# dram_lpddr4.net
KiCad netlist of a schematic drawn in Altium Designer
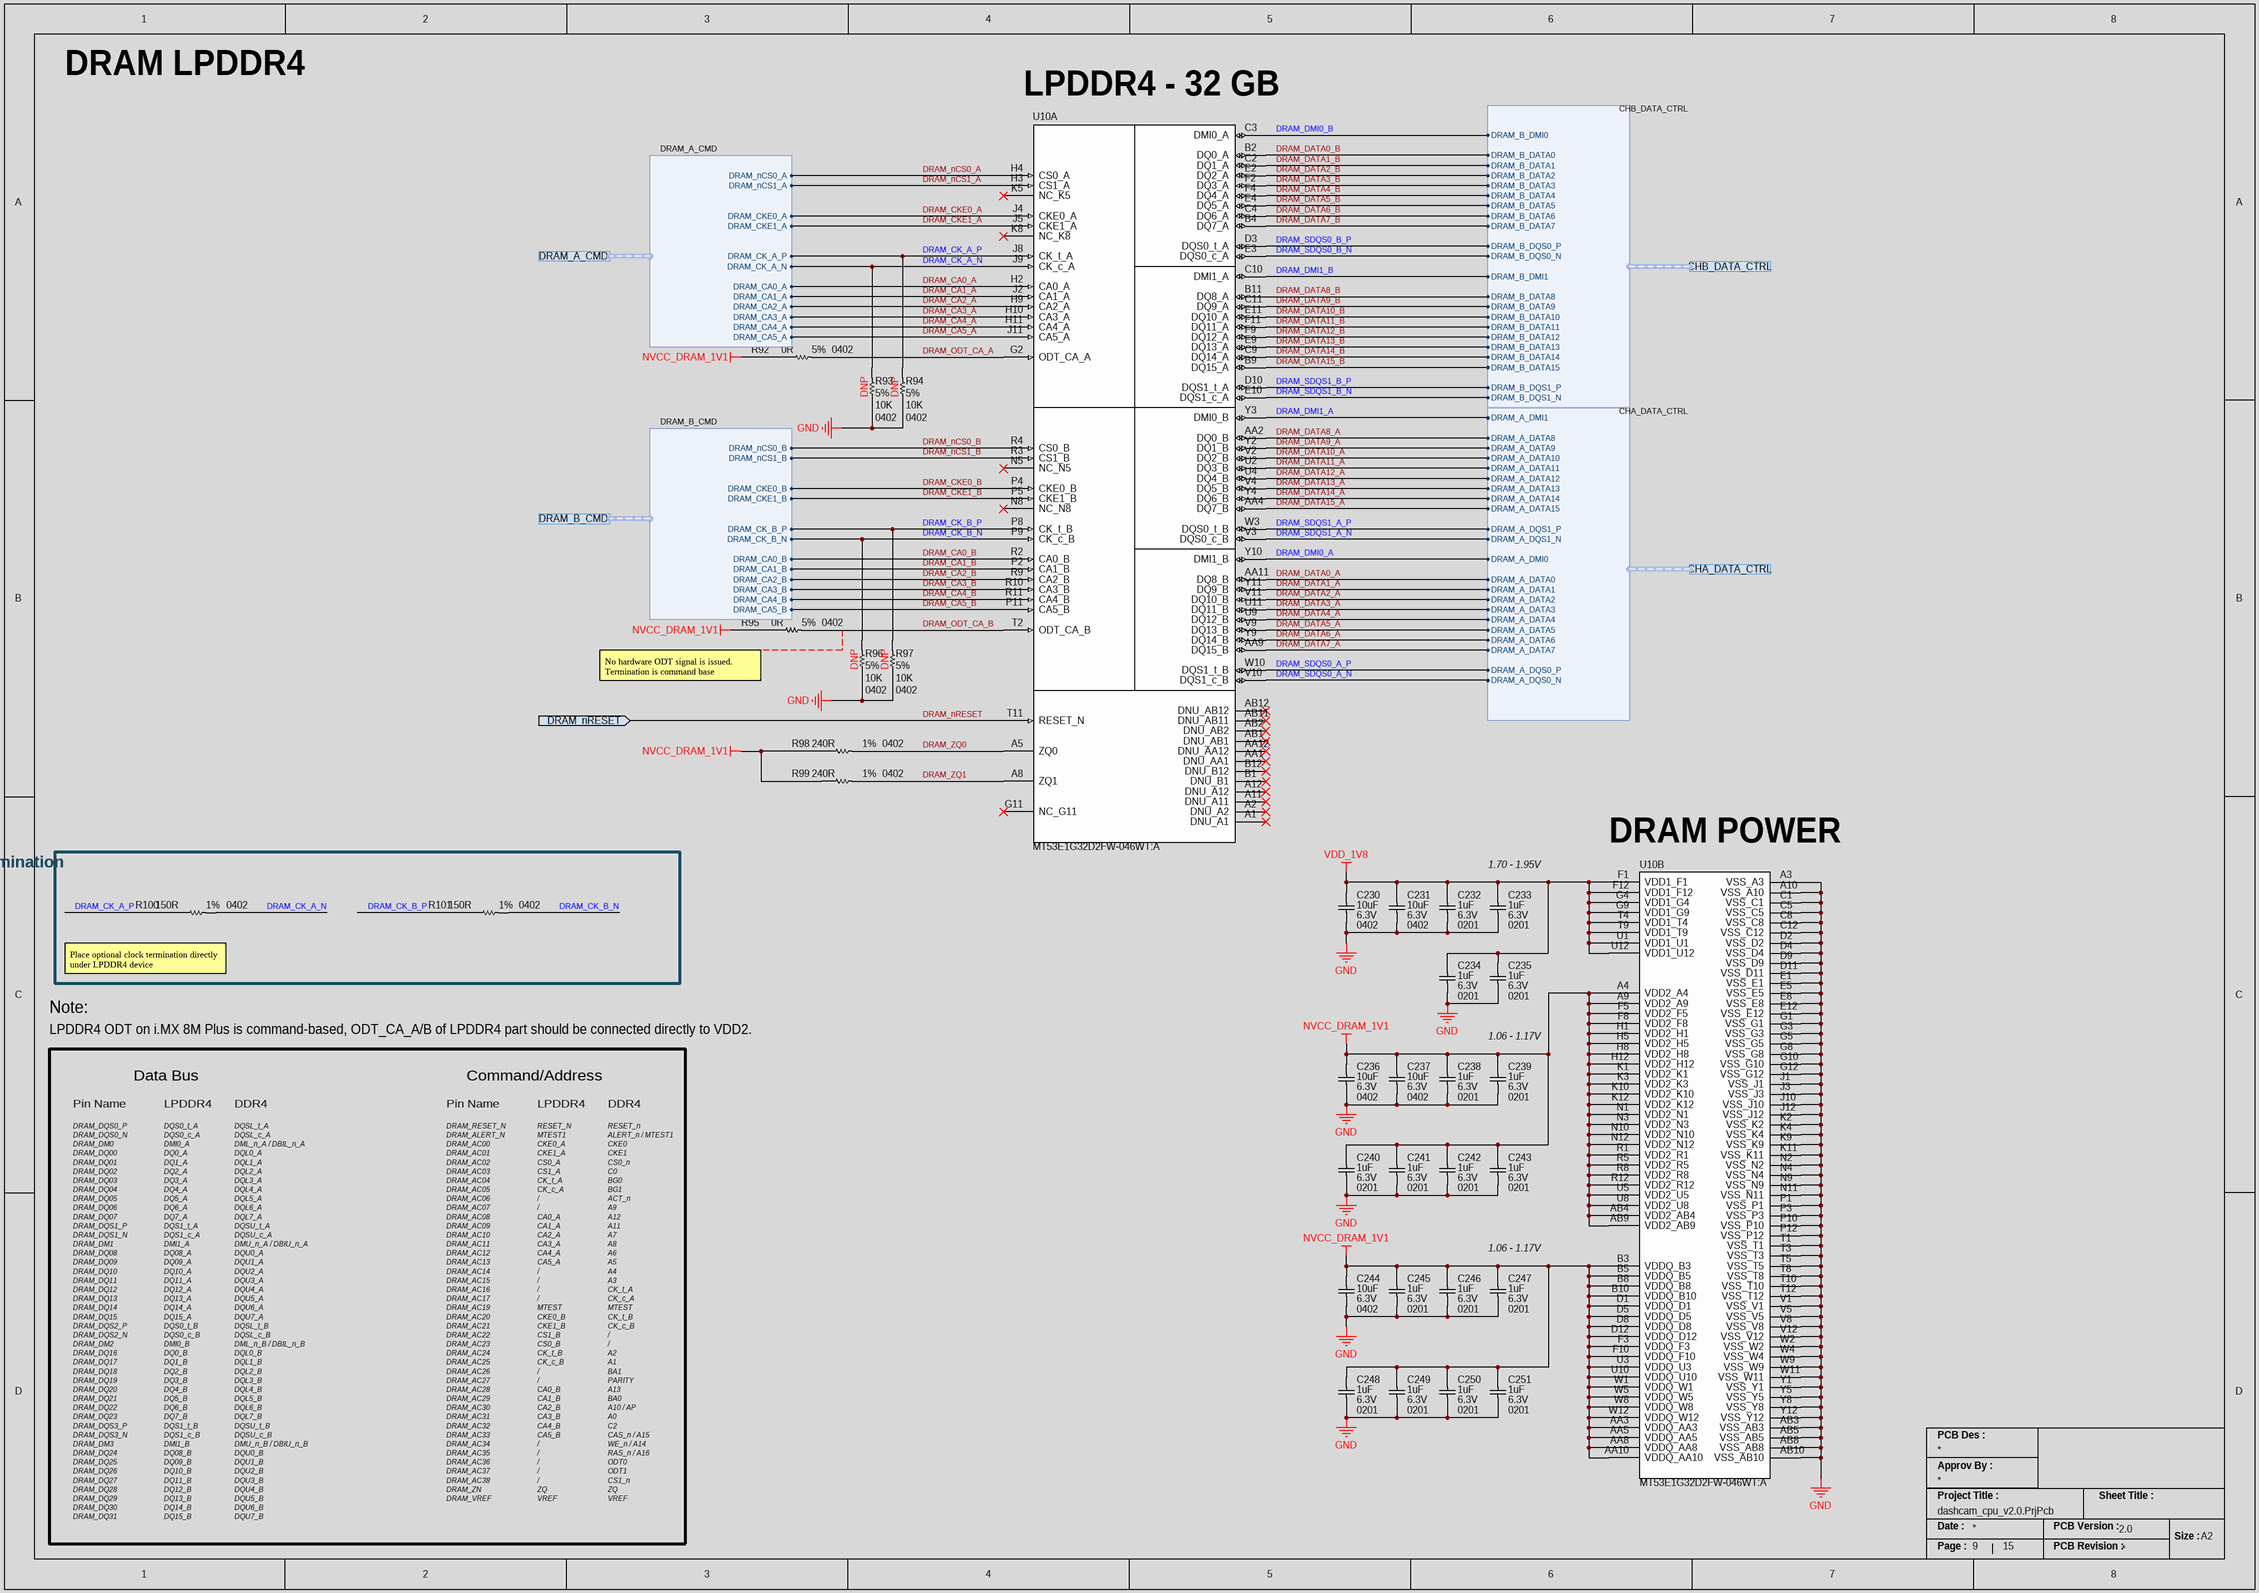
[diagram p0: dram_lpddr4.SchDoc]

(export (version "E")
  (design (tool "Eeschema 10.0.6"))
  (components
    (comp (ref "C230")
      (value "CL05A106MQ5NUNC")
      (footprint "CAP_0402_CAPC1005X05N")
      (description "Cap Ceramic 10uF 6.3V X5R 20% SMD 0402 85C T/R")
      (fields
        (field (name "MANUFACTURER") "Samsung")
        (field (name "TOLERANCE") "20%")
        (field (name "CASE/PACKAGE") "0402")
        (field (name "CAPACITANCE") "10uF")
        (field (name "VOLTAGE RATING") "6.3V")
      )
      (libsource (lib "Electronic Devices_LIB") (part "CAP_10UF_6.3V_X5R_0402"))
    )
    (comp (ref "C231")
      (value "CL05A106MQ5NUNC")
      (footprint "CAP_0402_CAPC1005X05N")
      (description "Cap Ceramic 10uF 6.3V X5R 20% SMD 0402 85C T/R")
      (fields
        (field (name "MANUFACTURER") "Samsung")
        (field (name "TOLERANCE") "20%")
        (field (name "CASE/PACKAGE") "0402")
        (field (name "CAPACITANCE") "10uF")
        (field (name "VOLTAGE RATING") "6.3V")
      )
      (libsource (lib "Electronic Devices_LIB") (part "CAP_10UF_6.3V_X5R_0402"))
    )
    (comp (ref "C232")
      (value "02016D105MAT2A")
      (footprint "CAP_0201_CAPC0603X03N")
      (description "0201 1 uF 6.3 V ±20 % Tolerance X5R Surface Mount Multilayer Ceramic Capacitor")
      (fields
        (field (name "MANUFACTURER") "Kyocera AVX")
        (field (name "TOLERANCE") "20%")
        (field (name "VOLTAGE RATING (DC)") "6.3V")
        (field (name "CAPACITANCE") "1uF")
        (field (name "CASE/PACKAGE") "0201")
      )
      (libsource (lib "Electronic Devices_LIB") (part "CAP_1UF_6.3V_X5R_0201"))
    )
    (comp (ref "C233")
      (value "02016D105MAT2A")
      (footprint "CAP_0201_CAPC0603X03N")
      (description "0201 1 uF 6.3 V ±20 % Tolerance X5R Surface Mount Multilayer Ceramic Capacitor")
      (fields
        (field (name "MANUFACTURER") "Kyocera AVX")
        (field (name "TOLERANCE") "20%")
        (field (name "VOLTAGE RATING (DC)") "6.3V")
        (field (name "CAPACITANCE") "1uF")
        (field (name "CASE/PACKAGE") "0201")
      )
      (libsource (lib "Electronic Devices_LIB") (part "CAP_1UF_6.3V_X5R_0201"))
    )
    (comp (ref "C234")
      (value "02016D105MAT2A")
      (footprint "CAP_0201_CAPC0603X03N")
      (description "0201 1 uF 6.3 V ±20 % Tolerance X5R Surface Mount Multilayer Ceramic Capacitor")
      (fields
        (field (name "MANUFACTURER") "Kyocera AVX")
        (field (name "TOLERANCE") "20%")
        (field (name "VOLTAGE RATING (DC)") "6.3V")
        (field (name "CAPACITANCE") "1uF")
        (field (name "CASE/PACKAGE") "0201")
      )
      (libsource (lib "Electronic Devices_LIB") (part "CAP_1UF_6.3V_X5R_0201"))
    )
    (comp (ref "C235")
      (value "02016D105MAT2A")
      (footprint "CAP_0201_CAPC0603X03N")
      (description "0201 1 uF 6.3 V ±20 % Tolerance X5R Surface Mount Multilayer Ceramic Capacitor")
      (fields
        (field (name "MANUFACTURER") "Kyocera AVX")
        (field (name "TOLERANCE") "20%")
        (field (name "VOLTAGE RATING (DC)") "6.3V")
        (field (name "CAPACITANCE") "1uF")
        (field (name "CASE/PACKAGE") "0201")
      )
      (libsource (lib "Electronic Devices_LIB") (part "CAP_1UF_6.3V_X5R_0201"))
    )
    (comp (ref "C236")
      (value "CL05A106MQ5NUNC")
      (footprint "CAP_0402_CAPC1005X05N")
      (description "Cap Ceramic 10uF 6.3V X5R 20% SMD 0402 85C T/R")
      (fields
        (field (name "MANUFACTURER") "Samsung")
        (field (name "TOLERANCE") "20%")
        (field (name "CASE/PACKAGE") "0402")
        (field (name "CAPACITANCE") "10uF")
        (field (name "VOLTAGE RATING") "6.3V")
      )
      (libsource (lib "Electronic Devices_LIB") (part "CAP_10UF_6.3V_X5R_0402"))
    )
    (comp (ref "C237")
      (value "CL05A106MQ5NUNC")
      (footprint "CAP_0402_CAPC1005X05N")
      (description "Cap Ceramic 10uF 6.3V X5R 20% SMD 0402 85C T/R")
      (fields
        (field (name "MANUFACTURER") "Samsung")
        (field (name "TOLERANCE") "20%")
        (field (name "CASE/PACKAGE") "0402")
        (field (name "CAPACITANCE") "10uF")
        (field (name "VOLTAGE RATING") "6.3V")
      )
      (libsource (lib "Electronic Devices_LIB") (part "CAP_10UF_6.3V_X5R_0402"))
    )
    (comp (ref "C238")
      (value "02016D105MAT2A")
      (footprint "CAP_0201_CAPC0603X03N")
      (description "0201 1 uF 6.3 V ±20 % Tolerance X5R Surface Mount Multilayer Ceramic Capacitor")
      (fields
        (field (name "MANUFACTURER") "Kyocera AVX")
        (field (name "TOLERANCE") "20%")
        (field (name "VOLTAGE RATING (DC)") "6.3V")
        (field (name "CAPACITANCE") "1uF")
        (field (name "CASE/PACKAGE") "0201")
      )
      (libsource (lib "Electronic Devices_LIB") (part "CAP_1UF_6.3V_X5R_0201"))
    )
    (comp (ref "C239")
      (value "02016D105MAT2A")
      (footprint "CAP_0201_CAPC0603X03N")
      (description "0201 1 uF 6.3 V ±20 % Tolerance X5R Surface Mount Multilayer Ceramic Capacitor")
      (fields
        (field (name "MANUFACTURER") "Kyocera AVX")
        (field (name "TOLERANCE") "20%")
        (field (name "VOLTAGE RATING (DC)") "6.3V")
        (field (name "CAPACITANCE") "1uF")
        (field (name "CASE/PACKAGE") "0201")
      )
      (libsource (lib "Electronic Devices_LIB") (part "CAP_1UF_6.3V_X5R_0201"))
    )
    (comp (ref "C240")
      (value "02016D105MAT2A")
      (footprint "CAP_0201_CAPC0603X03N")
      (description "0201 1 uF 6.3 V ±20 % Tolerance X5R Surface Mount Multilayer Ceramic Capacitor")
      (fields
        (field (name "MANUFACTURER") "Kyocera AVX")
        (field (name "TOLERANCE") "20%")
        (field (name "VOLTAGE RATING (DC)") "6.3V")
        (field (name "CAPACITANCE") "1uF")
        (field (name "CASE/PACKAGE") "0201")
      )
      (libsource (lib "Electronic Devices_LIB") (part "CAP_1UF_6.3V_X5R_0201"))
    )
    (comp (ref "C241")
      (value "02016D105MAT2A")
      (footprint "CAP_0201_CAPC0603X03N")
      (description "0201 1 uF 6.3 V ±20 % Tolerance X5R Surface Mount Multilayer Ceramic Capacitor")
      (fields
        (field (name "MANUFACTURER") "Kyocera AVX")
        (field (name "TOLERANCE") "20%")
        (field (name "VOLTAGE RATING (DC)") "6.3V")
        (field (name "CAPACITANCE") "1uF")
        (field (name "CASE/PACKAGE") "0201")
      )
      (libsource (lib "Electronic Devices_LIB") (part "CAP_1UF_6.3V_X5R_0201"))
    )
    (comp (ref "C242")
      (value "02016D105MAT2A")
      (footprint "CAP_0201_CAPC0603X03N")
      (description "0201 1 uF 6.3 V ±20 % Tolerance X5R Surface Mount Multilayer Ceramic Capacitor")
      (fields
        (field (name "MANUFACTURER") "Kyocera AVX")
        (field (name "TOLERANCE") "20%")
        (field (name "VOLTAGE RATING (DC)") "6.3V")
        (field (name "CAPACITANCE") "1uF")
        (field (name "CASE/PACKAGE") "0201")
      )
      (libsource (lib "Electronic Devices_LIB") (part "CAP_1UF_6.3V_X5R_0201"))
    )
    (comp (ref "C243")
      (value "02016D105MAT2A")
      (footprint "CAP_0201_CAPC0603X03N")
      (description "0201 1 uF 6.3 V ±20 % Tolerance X5R Surface Mount Multilayer Ceramic Capacitor")
      (fields
        (field (name "MANUFACTURER") "Kyocera AVX")
        (field (name "TOLERANCE") "20%")
        (field (name "VOLTAGE RATING (DC)") "6.3V")
        (field (name "CAPACITANCE") "1uF")
        (field (name "CASE/PACKAGE") "0201")
      )
      (libsource (lib "Electronic Devices_LIB") (part "CAP_1UF_6.3V_X5R_0201"))
    )
    (comp (ref "C244")
      (value "CL05A106MQ5NUNC")
      (footprint "CAP_0402_CAPC1005X05N")
      (description "Cap Ceramic 10uF 6.3V X5R 20% SMD 0402 85C T/R")
      (fields
        (field (name "MANUFACTURER") "Samsung")
        (field (name "TOLERANCE") "20%")
        (field (name "CASE/PACKAGE") "0402")
        (field (name "CAPACITANCE") "10uF")
        (field (name "VOLTAGE RATING") "6.3V")
      )
      (libsource (lib "Electronic Devices_LIB") (part "CAP_10UF_6.3V_X5R_0402"))
    )
    (comp (ref "C245")
      (value "02016D105MAT2A")
      (footprint "CAP_0201_CAPC0603X03N")
      (description "0201 1 uF 6.3 V ±20 % Tolerance X5R Surface Mount Multilayer Ceramic Capacitor")
      (fields
        (field (name "MANUFACTURER") "Kyocera AVX")
        (field (name "TOLERANCE") "20%")
        (field (name "VOLTAGE RATING (DC)") "6.3V")
        (field (name "CAPACITANCE") "1uF")
        (field (name "CASE/PACKAGE") "0201")
      )
      (libsource (lib "Electronic Devices_LIB") (part "CAP_1UF_6.3V_X5R_0201"))
    )
    (comp (ref "C246")
      (value "02016D105MAT2A")
      (footprint "CAP_0201_CAPC0603X03N")
      (description "0201 1 uF 6.3 V ±20 % Tolerance X5R Surface Mount Multilayer Ceramic Capacitor")
      (fields
        (field (name "MANUFACTURER") "Kyocera AVX")
        (field (name "TOLERANCE") "20%")
        (field (name "VOLTAGE RATING (DC)") "6.3V")
        (field (name "CAPACITANCE") "1uF")
        (field (name "CASE/PACKAGE") "0201")
      )
      (libsource (lib "Electronic Devices_LIB") (part "CAP_1UF_6.3V_X5R_0201"))
    )
    (comp (ref "C247")
      (value "02016D105MAT2A")
      (footprint "CAP_0201_CAPC0603X03N")
      (description "0201 1 uF 6.3 V ±20 % Tolerance X5R Surface Mount Multilayer Ceramic Capacitor")
      (fields
        (field (name "MANUFACTURER") "Kyocera AVX")
        (field (name "TOLERANCE") "20%")
        (field (name "VOLTAGE RATING (DC)") "6.3V")
        (field (name "CAPACITANCE") "1uF")
        (field (name "CASE/PACKAGE") "0201")
      )
      (libsource (lib "Electronic Devices_LIB") (part "CAP_1UF_6.3V_X5R_0201"))
    )
    (comp (ref "C248")
      (value "02016D105MAT2A")
      (footprint "CAP_0201_CAPC0603X03N")
      (description "0201 1 uF 6.3 V ±20 % Tolerance X5R Surface Mount Multilayer Ceramic Capacitor")
      (fields
        (field (name "MANUFACTURER") "Kyocera AVX")
        (field (name "TOLERANCE") "20%")
        (field (name "VOLTAGE RATING (DC)") "6.3V")
        (field (name "CAPACITANCE") "1uF")
        (field (name "CASE/PACKAGE") "0201")
      )
      (libsource (lib "Electronic Devices_LIB") (part "CAP_1UF_6.3V_X5R_0201"))
    )
    (comp (ref "C249")
      (value "02016D105MAT2A")
      (footprint "CAP_0201_CAPC0603X03N")
      (description "0201 1 uF 6.3 V ±20 % Tolerance X5R Surface Mount Multilayer Ceramic Capacitor")
      (fields
        (field (name "MANUFACTURER") "Kyocera AVX")
        (field (name "TOLERANCE") "20%")
        (field (name "VOLTAGE RATING (DC)") "6.3V")
        (field (name "CAPACITANCE") "1uF")
        (field (name "CASE/PACKAGE") "0201")
      )
      (libsource (lib "Electronic Devices_LIB") (part "CAP_1UF_6.3V_X5R_0201"))
    )
    (comp (ref "C250")
      (value "02016D105MAT2A")
      (footprint "CAP_0201_CAPC0603X03N")
      (description "0201 1 uF 6.3 V ±20 % Tolerance X5R Surface Mount Multilayer Ceramic Capacitor")
      (fields
        (field (name "MANUFACTURER") "Kyocera AVX")
        (field (name "TOLERANCE") "20%")
        (field (name "VOLTAGE RATING (DC)") "6.3V")
        (field (name "CAPACITANCE") "1uF")
        (field (name "CASE/PACKAGE") "0201")
      )
      (libsource (lib "Electronic Devices_LIB") (part "CAP_1UF_6.3V_X5R_0201"))
    )
    (comp (ref "C251")
      (value "02016D105MAT2A")
      (footprint "CAP_0201_CAPC0603X03N")
      (description "0201 1 uF 6.3 V ±20 % Tolerance X5R Surface Mount Multilayer Ceramic Capacitor")
      (fields
        (field (name "MANUFACTURER") "Kyocera AVX")
        (field (name "TOLERANCE") "20%")
        (field (name "VOLTAGE RATING (DC)") "6.3V")
        (field (name "CAPACITANCE") "1uF")
        (field (name "CASE/PACKAGE") "0201")
      )
      (libsource (lib "Electronic Devices_LIB") (part "CAP_1UF_6.3V_X5R_0201"))
    )
    (comp (ref "R92")
      (value "ERJ-2GE0R00X")
      (footprint "RES_0402_RESC1005X04N")
      (description "SMD Chip Resistor, Jumper, 0 ohm, 100 mW, 0402 [1005 Metric], Thick Film, General Purpose")
      (fields
        (field (name "MANUFACTURER") "Panasonic")
        (field (name "CASE CODE (IMPERIAL)") "0402")
        (field (name "TOLERANCE") "5%")
        (field (name "RESISTANCE") "0R")
      )
      (libsource (lib "Electronic Devices_LIB") (part "RES_0R_5%_100mW_0402"))
    )
    (comp (ref "R93")
      (value "ERJ-2GEJ103X")
      (footprint "RES_0402_RESC1005X04N")
      (description "Res Thick Film 0402 10K Ohm 5% 1/10W ±200ppm/°C Molded SMD Punched Carrier T/R")
      (fields
        (field (name "MANUFACTURER") "Panasonic")
        (field (name "TOLERANCE") "5%")
        (field (name "RESISTANCE") "10K")
        (field (name "CASE/PACKAGE") "0402")
      )
      (libsource (lib "Electronic Devices_LIB") (part "RES_10K_5%_100mW_0402"))
    )
    (comp (ref "R94")
      (value "ERJ-2GEJ103X")
      (footprint "RES_0402_RESC1005X04N")
      (description "Res Thick Film 0402 10K Ohm 5% 1/10W ±200ppm/°C Molded SMD Punched Carrier T/R")
      (fields
        (field (name "MANUFACTURER") "Panasonic")
        (field (name "TOLERANCE") "5%")
        (field (name "RESISTANCE") "10K")
        (field (name "CASE/PACKAGE") "0402")
      )
      (libsource (lib "Electronic Devices_LIB") (part "RES_10K_5%_100mW_0402"))
    )
    (comp (ref "R95")
      (value "ERJ-2GE0R00X")
      (footprint "RES_0402_RESC1005X04N")
      (description "SMD Chip Resistor, Jumper, 0 ohm, 100 mW, 0402 [1005 Metric], Thick Film, General Purpose")
      (fields
        (field (name "MANUFACTURER") "Panasonic")
        (field (name "CASE CODE (IMPERIAL)") "0402")
        (field (name "TOLERANCE") "5%")
        (field (name "RESISTANCE") "0R")
      )
      (libsource (lib "Electronic Devices_LIB") (part "RES_0R_5%_100mW_0402"))
    )
    (comp (ref "R96")
      (value "ERJ-2GEJ103X")
      (footprint "RES_0402_RESC1005X04N")
      (description "Res Thick Film 0402 10K Ohm 5% 1/10W ±200ppm/°C Molded SMD Punched Carrier T/R")
      (fields
        (field (name "MANUFACTURER") "Panasonic")
        (field (name "TOLERANCE") "5%")
        (field (name "RESISTANCE") "10K")
        (field (name "CASE/PACKAGE") "0402")
      )
      (libsource (lib "Electronic Devices_LIB") (part "RES_10K_5%_100mW_0402"))
    )
    (comp (ref "R97")
      (value "ERJ-2GEJ103X")
      (footprint "RES_0402_RESC1005X04N")
      (description "Res Thick Film 0402 10K Ohm 5% 1/10W ±200ppm/°C Molded SMD Punched Carrier T/R")
      (fields
        (field (name "MANUFACTURER") "Panasonic")
        (field (name "TOLERANCE") "5%")
        (field (name "RESISTANCE") "10K")
        (field (name "CASE/PACKAGE") "0402")
      )
      (libsource (lib "Electronic Devices_LIB") (part "RES_10K_5%_100mW_0402"))
    )
    (comp (ref "R98")
      (value "RC0402FR-07240RL")
      (footprint "RES_0402_RESC1005X04N")
      (description "SMD Chip Resistor, 240 Ohm, ± 1%, 63 mW, 0402 [1005 Metric], Thick Film, General Purpose")
      (fields
        (field (name "MANUFACTURER") "Yageo")
        (field (name "TOLERANCE") "1%")
        (field (name "RESISTANCE") "240R")
        (field (name "CASE/PACKAGE") "0402")
      )
      (libsource (lib "Electronic Devices_LIB") (part "RES_240R_1%_63mW_0402"))
    )
    (comp (ref "R99")
      (value "RC0402FR-07240RL")
      (footprint "RES_0402_RESC1005X04N")
      (description "SMD Chip Resistor, 240 Ohm, ± 1%, 63 mW, 0402 [1005 Metric], Thick Film, General Purpose")
      (fields
        (field (name "MANUFACTURER") "Yageo")
        (field (name "TOLERANCE") "1%")
        (field (name "RESISTANCE") "240R")
        (field (name "CASE/PACKAGE") "0402")
      )
      (libsource (lib "Electronic Devices_LIB") (part "RES_240R_1%_63mW_0402"))
    )
    (comp (ref "R100")
      (value "CR0402-FX-1500GLF")
      (footprint "RES_0402_RESC1005X04N")
      (description "SMD Chip Resistor, 150 Ohm, ± 1%, 63 mW, 0402 [1005 Metric], Thick Film, General Purpose")
      (fields
        (field (name "MANUFACTURER") "Bourns")
        (field (name "TOLERANCE") "1%")
        (field (name "RESISTANCE") "150R")
        (field (name "CASE/PACKAGE") "0402")
      )
      (libsource (lib "Electronic Devices_LIB") (part "RES_150R_1%_63mW_0402"))
    )
    (comp (ref "R101")
      (value "CR0402-FX-1500GLF")
      (footprint "RES_0402_RESC1005X04N")
      (description "SMD Chip Resistor, 150 Ohm, ± 1%, 63 mW, 0402 [1005 Metric], Thick Film, General Purpose")
      (fields
        (field (name "MANUFACTURER") "Bourns")
        (field (name "TOLERANCE") "1%")
        (field (name "RESISTANCE") "150R")
        (field (name "CASE/PACKAGE") "0402")
      )
      (libsource (lib "Electronic Devices_LIB") (part "RES_150R_1%_63mW_0402"))
    )
    (comp (ref "U10")
      (value "MT53E1G32D2FW-046WT:A")
      (footprint "IC_DRAM_BGA200_0P65X0P8_10P1X14P6")
      (description "LPDDR4 32G 1GX32 FBGA DDP")
      (fields (field (name "MANUFACTURER") "Micron Technology"))
      (libsource (lib "Electronic Devices_LIB") (part "IC_DRAM_32G_MT53E1G32D2FW-046WT{colon}A"))
    )
  )
  (nets
    (net (code "5") (name "/DRAM_CA0_A") (class "Default")
      (node (ref "U10") (pin "H2") (pinfunction "CA0_A_H2") (pintype "input"))
    )
    (net (code "6") (name "/DRAM_CA0_B") (class "Default")
      (node (ref "U10") (pin "R2") (pinfunction "CA0_B_R2") (pintype "input"))
    )
    (net (code "7") (name "/DRAM_CA1_A") (class "Default")
      (node (ref "U10") (pin "J2") (pinfunction "CA1_A_J2") (pintype "input"))
    )
    (net (code "8") (name "/DRAM_CA1_B") (class "Default")
      (node (ref "U10") (pin "P2") (pinfunction "CA1_B_P2") (pintype "input"))
    )
    (net (code "9") (name "/DRAM_CA2_A") (class "Default")
      (node (ref "U10") (pin "H9") (pinfunction "CA2_A_H9") (pintype "input"))
    )
    (net (code "10") (name "/DRAM_CA2_B") (class "Default")
      (node (ref "U10") (pin "R9") (pinfunction "CA2_B_R9") (pintype "input"))
    )
    (net (code "11") (name "/DRAM_CA3_A") (class "Default")
      (node (ref "U10") (pin "H10") (pinfunction "CA3_A_H10") (pintype "input"))
    )
    (net (code "12") (name "/DRAM_CA3_B") (class "Default")
      (node (ref "U10") (pin "R10") (pinfunction "CA3_B_R10") (pintype "input"))
    )
    (net (code "13") (name "/DRAM_CA4_A") (class "Default")
      (node (ref "U10") (pin "H11") (pinfunction "CA4_A_H11") (pintype "input"))
    )
    (net (code "14") (name "/DRAM_CA4_B") (class "Default")
      (node (ref "U10") (pin "R11") (pinfunction "CA4_B_R11") (pintype "input"))
    )
    (net (code "15") (name "/DRAM_CA5_A") (class "Default")
      (node (ref "U10") (pin "J11") (pinfunction "CA5_A_J11") (pintype "input"))
    )
    (net (code "16") (name "/DRAM_CA5_B") (class "Default")
      (node (ref "U10") (pin "P11") (pinfunction "CA5_B_P11") (pintype "input"))
    )
    (net (code "17") (name "/DRAM_CKE0_A") (class "Default")
      (node (ref "U10") (pin "J4") (pinfunction "CKE0_A_J4") (pintype "input"))
    )
    (net (code "18") (name "/DRAM_CKE0_B") (class "Default")
      (node (ref "U10") (pin "P4") (pinfunction "CKE0_B_P4") (pintype "input"))
    )
    (net (code "19") (name "/DRAM_CKE1_A") (class "Default")
      (node (ref "U10") (pin "J5") (pinfunction "CKE1_A_J5") (pintype "input"))
    )
    (net (code "20") (name "/DRAM_CKE1_B") (class "Default")
      (node (ref "U10") (pin "P5") (pinfunction "CKE1_B_P5") (pintype "input"))
    )
    (net (code "21") (name "/DRAM_CK_A_N") (class "Default")
      (node (ref "R100") (pin "2") (pinfunction "2_2") (pintype "passive"))
      (node (ref "R93") (pin "2") (pinfunction "2_2") (pintype "passive"))
      (node (ref "U10") (pin "J9") (pinfunction "CK_c_A_J9") (pintype "input"))
    )
    (net (code "22") (name "/DRAM_CK_A_P") (class "Default")
      (node (ref "R100") (pin "1") (pinfunction "1_1") (pintype "passive"))
      (node (ref "R94") (pin "2") (pinfunction "2_2") (pintype "passive"))
      (node (ref "U10") (pin "J8") (pinfunction "CK_t_A_J8") (pintype "input"))
    )
    (net (code "23") (name "/DRAM_CK_B_N") (class "Default")
      (node (ref "R101") (pin "2") (pinfunction "2_2") (pintype "passive"))
      (node (ref "R96") (pin "2") (pinfunction "2_2") (pintype "passive"))
      (node (ref "U10") (pin "P9") (pinfunction "CK_c_B_P9") (pintype "input"))
    )
    (net (code "24") (name "/DRAM_CK_B_P") (class "Default")
      (node (ref "R101") (pin "1") (pinfunction "1_1") (pintype "passive"))
      (node (ref "R97") (pin "2") (pinfunction "2_2") (pintype "passive"))
      (node (ref "U10") (pin "P8") (pinfunction "CK_t_B_P8") (pintype "input"))
    )
    (net (code "25") (name "/DRAM_DATA0_A") (class "Default")
      (node (ref "U10") (pin "AA11") (pinfunction "DQ8_B_AA11") (pintype "bidirectional"))
    )
    (net (code "26") (name "/DRAM_DATA0_B") (class "Default")
      (node (ref "U10") (pin "B2") (pinfunction "DQ0_A_B2") (pintype "bidirectional"))
    )
    (net (code "27") (name "/DRAM_DATA1_A") (class "Default")
      (node (ref "U10") (pin "Y11") (pinfunction "DQ9_B_Y11") (pintype "bidirectional"))
    )
    (net (code "28") (name "/DRAM_DATA1_B") (class "Default")
      (node (ref "U10") (pin "C2") (pinfunction "DQ1_A_C2") (pintype "bidirectional"))
    )
    (net (code "29") (name "/DRAM_DATA2_A") (class "Default")
      (node (ref "U10") (pin "V11") (pinfunction "DQ10_B_V11") (pintype "bidirectional"))
    )
    (net (code "30") (name "/DRAM_DATA2_B") (class "Default")
      (node (ref "U10") (pin "E2") (pinfunction "DQ2_A_E2") (pintype "bidirectional"))
    )
    (net (code "31") (name "/DRAM_DATA3_A") (class "Default")
      (node (ref "U10") (pin "U11") (pinfunction "DQ11_B_U11") (pintype "bidirectional"))
    )
    (net (code "32") (name "/DRAM_DATA3_B") (class "Default")
      (node (ref "U10") (pin "F2") (pinfunction "DQ3_A_F2") (pintype "bidirectional"))
    )
    (net (code "33") (name "/DRAM_DATA4_A") (class "Default")
      (node (ref "U10") (pin "U9") (pinfunction "DQ12_B_U9") (pintype "bidirectional"))
    )
    (net (code "34") (name "/DRAM_DATA4_B") (class "Default")
      (node (ref "U10") (pin "F4") (pinfunction "DQ4_A_F4") (pintype "bidirectional"))
    )
    (net (code "35") (name "/DRAM_DATA5_A") (class "Default")
      (node (ref "U10") (pin "V9") (pinfunction "DQ13_B_V9") (pintype "bidirectional"))
    )
    (net (code "36") (name "/DRAM_DATA5_B") (class "Default")
      (node (ref "U10") (pin "E4") (pinfunction "DQ5_A_E4") (pintype "bidirectional"))
    )
    (net (code "37") (name "/DRAM_DATA6_A") (class "Default")
      (node (ref "U10") (pin "Y9") (pinfunction "DQ14_B_Y9") (pintype "bidirectional"))
    )
    (net (code "38") (name "/DRAM_DATA6_B") (class "Default")
      (node (ref "U10") (pin "C4") (pinfunction "DQ6_A_C4") (pintype "bidirectional"))
    )
    (net (code "39") (name "/DRAM_DATA7_A") (class "Default")
      (node (ref "U10") (pin "AA9") (pinfunction "DQ15_B_AA9") (pintype "bidirectional"))
    )
    (net (code "40") (name "/DRAM_DATA7_B") (class "Default")
      (node (ref "U10") (pin "B4") (pinfunction "DQ7_A_B4") (pintype "bidirectional"))
    )
    (net (code "41") (name "/DRAM_DATA8_A") (class "Default")
      (node (ref "U10") (pin "AA2") (pinfunction "DQ0_B_AA2") (pintype "bidirectional"))
    )
    (net (code "42") (name "/DRAM_DATA8_B") (class "Default")
      (node (ref "U10") (pin "B11") (pinfunction "DQ8_A_B11") (pintype "bidirectional"))
    )
    (net (code "43") (name "/DRAM_DATA9_A") (class "Default")
      (node (ref "U10") (pin "Y2") (pinfunction "DQ1_B_Y2") (pintype "bidirectional"))
    )
    (net (code "44") (name "/DRAM_DATA9_B") (class "Default")
      (node (ref "U10") (pin "C11") (pinfunction "DQ9_A_C11") (pintype "bidirectional"))
    )
    (net (code "45") (name "/DRAM_DATA10_A") (class "Default")
      (node (ref "U10") (pin "V2") (pinfunction "DQ2_B_V2") (pintype "bidirectional"))
    )
    (net (code "46") (name "/DRAM_DATA10_B") (class "Default")
      (node (ref "U10") (pin "E11") (pinfunction "DQ10_A_E11") (pintype "bidirectional"))
    )
    (net (code "47") (name "/DRAM_DATA11_A") (class "Default")
      (node (ref "U10") (pin "U2") (pinfunction "DQ3_B_U2") (pintype "bidirectional"))
    )
    (net (code "48") (name "/DRAM_DATA11_B") (class "Default")
      (node (ref "U10") (pin "F11") (pinfunction "DQ11_A_F11") (pintype "bidirectional"))
    )
    (net (code "49") (name "/DRAM_DATA12_A") (class "Default")
      (node (ref "U10") (pin "U4") (pinfunction "DQ4_B_U4") (pintype "bidirectional"))
    )
    (net (code "50") (name "/DRAM_DATA12_B") (class "Default")
      (node (ref "U10") (pin "F9") (pinfunction "DQ12_A_F9") (pintype "bidirectional"))
    )
    (net (code "51") (name "/DRAM_DATA13_A") (class "Default")
      (node (ref "U10") (pin "V4") (pinfunction "DQ5_B_V4") (pintype "bidirectional"))
    )
    (net (code "52") (name "/DRAM_DATA13_B") (class "Default")
      (node (ref "U10") (pin "E9") (pinfunction "DQ13_A_E9") (pintype "bidirectional"))
    )
    (net (code "53") (name "/DRAM_DATA14_A") (class "Default")
      (node (ref "U10") (pin "Y4") (pinfunction "DQ6_B_Y4") (pintype "bidirectional"))
    )
    (net (code "54") (name "/DRAM_DATA14_B") (class "Default")
      (node (ref "U10") (pin "C9") (pinfunction "DQ14_A_C9") (pintype "bidirectional"))
    )
    (net (code "55") (name "/DRAM_DATA15_A") (class "Default")
      (node (ref "U10") (pin "AA4") (pinfunction "DQ7_B_AA4") (pintype "bidirectional"))
    )
    (net (code "56") (name "/DRAM_DATA15_B") (class "Default")
      (node (ref "U10") (pin "B9") (pinfunction "DQ15_A_B9") (pintype "bidirectional"))
    )
    (net (code "57") (name "/DRAM_DMI0_A") (class "Default")
      (node (ref "U10") (pin "Y10") (pinfunction "DMI1_B_Y10") (pintype "bidirectional"))
    )
    (net (code "58") (name "/DRAM_DMI0_B") (class "Default")
      (node (ref "U10") (pin "C3") (pinfunction "DMI0_A_C3") (pintype "bidirectional"))
    )
    (net (code "59") (name "/DRAM_DMI1_A") (class "Default")
      (node (ref "U10") (pin "Y3") (pinfunction "DMI0_B_Y3") (pintype "bidirectional"))
    )
    (net (code "60") (name "/DRAM_DMI1_B") (class "Default")
      (node (ref "U10") (pin "C10") (pinfunction "DMI1_A_C10") (pintype "bidirectional"))
    )
    (net (code "61") (name "/DRAM_ODT_CA_A") (class "Default")
      (node (ref "R92") (pin "2") (pinfunction "2_2") (pintype "passive"))
      (node (ref "U10") (pin "G2") (pinfunction "ODT_CA_A_G2") (pintype "input"))
    )
    (net (code "62") (name "/DRAM_ODT_CA_B") (class "Default")
      (node (ref "R95") (pin "2") (pinfunction "2_2") (pintype "passive"))
      (node (ref "U10") (pin "T2") (pinfunction "ODT_CA_B_T2") (pintype "input"))
    )
    (net (code "63") (name "/DRAM_SDQS0_A_N") (class "Default")
      (node (ref "U10") (pin "V10") (pinfunction "DQS1_c_B_V10") (pintype "bidirectional"))
    )
    (net (code "64") (name "/DRAM_SDQS0_A_P") (class "Default")
      (node (ref "U10") (pin "W10") (pinfunction "DQS1_t_B_W10") (pintype "bidirectional"))
    )
    (net (code "65") (name "/DRAM_SDQS0_B_N") (class "Default")
      (node (ref "U10") (pin "E3") (pinfunction "DQS0_c_A_E3") (pintype "bidirectional"))
    )
    (net (code "66") (name "/DRAM_SDQS0_B_P") (class "Default")
      (node (ref "U10") (pin "D3") (pinfunction "DQS0_t_A_D3") (pintype "bidirectional"))
    )
    (net (code "67") (name "/DRAM_SDQS1_A_N") (class "Default")
      (node (ref "U10") (pin "V3") (pinfunction "DQS0_c_B_V3") (pintype "bidirectional"))
    )
    (net (code "68") (name "/DRAM_SDQS1_A_P") (class "Default")
      (node (ref "U10") (pin "W3") (pinfunction "DQS0_t_B_W3") (pintype "bidirectional"))
    )
    (net (code "69") (name "/DRAM_SDQS1_B_N") (class "Default")
      (node (ref "U10") (pin "E10") (pinfunction "DQS1_c_A_E10") (pintype "bidirectional"))
    )
    (net (code "70") (name "/DRAM_SDQS1_B_P") (class "Default")
      (node (ref "U10") (pin "D10") (pinfunction "DQS1_t_A_D10") (pintype "bidirectional"))
    )
    (net (code "71") (name "/DRAM_ZQ0") (class "Default")
      (node (ref "R98") (pin "2") (pinfunction "2_2") (pintype "passive"))
      (node (ref "U10") (pin "A5") (pinfunction "ZQ0_A5") (pintype "passive"))
    )
    (net (code "72") (name "/DRAM_ZQ1") (class "Default")
      (node (ref "R99") (pin "2") (pinfunction "2_2") (pintype "passive"))
      (node (ref "U10") (pin "A8") (pinfunction "ZQ1_A8") (pintype "passive"))
    )
    (net (code "73") (name "/DRAM_nCS0_A") (class "Default")
      (node (ref "U10") (pin "H4") (pinfunction "CS0_A_H4") (pintype "input"))
    )
    (net (code "74") (name "/DRAM_nCS0_B") (class "Default")
      (node (ref "U10") (pin "R4") (pinfunction "CS0_B_R4") (pintype "input"))
    )
    (net (code "75") (name "/DRAM_nCS1_A") (class "Default")
      (node (ref "U10") (pin "H3") (pinfunction "CS1_A_H3") (pintype "input"))
    )
    (net (code "76") (name "/DRAM_nCS1_B") (class "Default")
      (node (ref "U10") (pin "R3") (pinfunction "CS1_B_R3") (pintype "input"))
    )
    (net (code "77") (name "/DRAM_nRESET") (class "Default")
      (node (ref "U10") (pin "T11") (pinfunction "RESET_N_T11") (pintype "input"))
    )
    (net (code "82") (name "GND") (class "Default")
      (node (ref "C230") (pin "1") (pinfunction "1_1") (pintype "passive"))
      (node (ref "C231") (pin "1") (pinfunction "1_1") (pintype "passive"))
      (node (ref "C232") (pin "1") (pinfunction "1_1") (pintype "passive"))
      (node (ref "C233") (pin "1") (pinfunction "1_1") (pintype "passive"))
      (node (ref "C234") (pin "1") (pinfunction "1_1") (pintype "passive"))
      (node (ref "C235") (pin "1") (pinfunction "1_1") (pintype "passive"))
      (node (ref "C236") (pin "1") (pinfunction "1_1") (pintype "passive"))
      (node (ref "C237") (pin "1") (pinfunction "1_1") (pintype "passive"))
      (node (ref "C238") (pin "1") (pinfunction "1_1") (pintype "passive"))
      (node (ref "C239") (pin "1") (pinfunction "1_1") (pintype "passive"))
      (node (ref "C240") (pin "1") (pinfunction "1_1") (pintype "passive"))
      (node (ref "C241") (pin "1") (pinfunction "1_1") (pintype "passive"))
      (node (ref "C242") (pin "1") (pinfunction "1_1") (pintype "passive"))
      (node (ref "C243") (pin "1") (pinfunction "1_1") (pintype "passive"))
      (node (ref "C244") (pin "1") (pinfunction "1_1") (pintype "passive"))
      (node (ref "C245") (pin "1") (pinfunction "1_1") (pintype "passive"))
      (node (ref "C246") (pin "1") (pinfunction "1_1") (pintype "passive"))
      (node (ref "C247") (pin "1") (pinfunction "1_1") (pintype "passive"))
      (node (ref "C248") (pin "1") (pinfunction "1_1") (pintype "passive"))
      (node (ref "C249") (pin "1") (pinfunction "1_1") (pintype "passive"))
      (node (ref "C250") (pin "1") (pinfunction "1_1") (pintype "passive"))
      (node (ref "C251") (pin "1") (pinfunction "1_1") (pintype "passive"))
      (node (ref "R93") (pin "1") (pinfunction "1_1") (pintype "passive"))
      (node (ref "R94") (pin "1") (pinfunction "1_1") (pintype "passive"))
      (node (ref "R96") (pin "1") (pinfunction "1_1") (pintype "passive"))
      (node (ref "R97") (pin "1") (pinfunction "1_1") (pintype "passive"))
      (node (ref "U10") (pin "A10") (pinfunction "VSS_A10_A10") (pintype "power_in"))
      (node (ref "U10") (pin "A3") (pinfunction "VSS_A3_A3") (pintype "power_in"))
      (node (ref "U10") (pin "AB10") (pinfunction "VSS_AB10_AB10") (pintype "power_in"))
      (node (ref "U10") (pin "AB3") (pinfunction "VSS_AB3_AB3") (pintype "power_in"))
      (node (ref "U10") (pin "AB5") (pinfunction "VSS_AB5_AB5") (pintype "power_in"))
      (node (ref "U10") (pin "AB8") (pinfunction "VSS_AB8_AB8") (pintype "power_in"))
      (node (ref "U10") (pin "C1") (pinfunction "VSS_C1_C1") (pintype "power_in"))
      (node (ref "U10") (pin "C12") (pinfunction "VSS_C12_C12") (pintype "power_in"))
      (node (ref "U10") (pin "C5") (pinfunction "VSS_C5_C5") (pintype "power_in"))
      (node (ref "U10") (pin "C8") (pinfunction "VSS_C8_C8") (pintype "power_in"))
      (node (ref "U10") (pin "D11") (pinfunction "VSS_D11_D11") (pintype "power_in"))
      (node (ref "U10") (pin "D2") (pinfunction "VSS_D2_D2") (pintype "power_in"))
      (node (ref "U10") (pin "D4") (pinfunction "VSS_D4_D4") (pintype "power_in"))
      (node (ref "U10") (pin "D9") (pinfunction "VSS_D9_D9") (pintype "power_in"))
      (node (ref "U10") (pin "E1") (pinfunction "VSS_E1_E1") (pintype "power_in"))
      (node (ref "U10") (pin "E12") (pinfunction "VSS_E12_E12") (pintype "power_in"))
      (node (ref "U10") (pin "E5") (pinfunction "VSS_E5_E5") (pintype "power_in"))
      (node (ref "U10") (pin "E8") (pinfunction "VSS_E8_E8") (pintype "power_in"))
      (node (ref "U10") (pin "G1") (pinfunction "VSS_G1_G1") (pintype "power_in"))
      (node (ref "U10") (pin "G10") (pinfunction "VSS_G10_G10") (pintype "power_in"))
      (node (ref "U10") (pin "G12") (pinfunction "VSS_G12_G12") (pintype "power_in"))
      (node (ref "U10") (pin "G3") (pinfunction "VSS_G3_G3") (pintype "power_in"))
      (node (ref "U10") (pin "G5") (pinfunction "VSS_G5_G5") (pintype "power_in"))
      (node (ref "U10") (pin "G8") (pinfunction "VSS_G8_G8") (pintype "power_in"))
      (node (ref "U10") (pin "J1") (pinfunction "VSS_J1_J1") (pintype "power_in"))
      (node (ref "U10") (pin "J10") (pinfunction "VSS_J10_J10") (pintype "power_in"))
      (node (ref "U10") (pin "J12") (pinfunction "VSS_J12_J12") (pintype "power_in"))
      (node (ref "U10") (pin "J3") (pinfunction "VSS_J3_J3") (pintype "power_in"))
      (node (ref "U10") (pin "K11") (pinfunction "VSS_K11_K11") (pintype "power_in"))
      (node (ref "U10") (pin "K2") (pinfunction "VSS_K2_K2") (pintype "power_in"))
      (node (ref "U10") (pin "K4") (pinfunction "VSS_K4_K4") (pintype "power_in"))
      (node (ref "U10") (pin "K9") (pinfunction "VSS_K9_K9") (pintype "power_in"))
      (node (ref "U10") (pin "N11") (pinfunction "VSS_N11_N11") (pintype "power_in"))
      (node (ref "U10") (pin "N2") (pinfunction "VSS_N2_N2") (pintype "power_in"))
      (node (ref "U10") (pin "N4") (pinfunction "VSS_N4_N4") (pintype "power_in"))
      (node (ref "U10") (pin "N9") (pinfunction "VSS_N9_N9") (pintype "power_in"))
      (node (ref "U10") (pin "P1") (pinfunction "VSS_P1_P1") (pintype "power_in"))
      (node (ref "U10") (pin "P10") (pinfunction "VSS_P10_P10") (pintype "power_in"))
      (node (ref "U10") (pin "P12") (pinfunction "VSS_P12_P12") (pintype "power_in"))
      (node (ref "U10") (pin "P3") (pinfunction "VSS_P3_P3") (pintype "power_in"))
      (node (ref "U10") (pin "T1") (pinfunction "VSS_T1_T1") (pintype "power_in"))
      (node (ref "U10") (pin "T10") (pinfunction "VSS_T10_T10") (pintype "power_in"))
      (node (ref "U10") (pin "T12") (pinfunction "VSS_T12_T12") (pintype "power_in"))
      (node (ref "U10") (pin "T3") (pinfunction "VSS_T3_T3") (pintype "power_in"))
      (node (ref "U10") (pin "T5") (pinfunction "VSS_T5_T5") (pintype "power_in"))
      (node (ref "U10") (pin "T8") (pinfunction "VSS_T8_T8") (pintype "power_in"))
      (node (ref "U10") (pin "V1") (pinfunction "VSS_V1_V1") (pintype "power_in"))
      (node (ref "U10") (pin "V12") (pinfunction "VSS_V12_V12") (pintype "power_in"))
      (node (ref "U10") (pin "V5") (pinfunction "VSS_V5_V5") (pintype "power_in"))
      (node (ref "U10") (pin "V8") (pinfunction "VSS_V8_V8") (pintype "power_in"))
      (node (ref "U10") (pin "W11") (pinfunction "VSS_W11_W11") (pintype "power_in"))
      (node (ref "U10") (pin "W2") (pinfunction "VSS_W2_W2") (pintype "power_in"))
      (node (ref "U10") (pin "W4") (pinfunction "VSS_W4_W4") (pintype "power_in"))
      (node (ref "U10") (pin "W9") (pinfunction "VSS_W9_W9") (pintype "power_in"))
      (node (ref "U10") (pin "Y1") (pinfunction "VSS_Y1_Y1") (pintype "power_in"))
      (node (ref "U10") (pin "Y12") (pinfunction "VSS_Y12_Y12") (pintype "power_in"))
      (node (ref "U10") (pin "Y5") (pinfunction "VSS_Y5_Y5") (pintype "power_in"))
      (node (ref "U10") (pin "Y8") (pinfunction "VSS_Y8_Y8") (pintype "power_in"))
    )
    (net (code "83") (name "NVCC_DRAM_1V1") (class "Default")
      (node (ref "C236") (pin "2") (pinfunction "2_2") (pintype "passive"))
      (node (ref "C237") (pin "2") (pinfunction "2_2") (pintype "passive"))
      (node (ref "C238") (pin "2") (pinfunction "2_2") (pintype "passive"))
      (node (ref "C239") (pin "2") (pinfunction "2_2") (pintype "passive"))
      (node (ref "C240") (pin "2") (pinfunction "2_2") (pintype "passive"))
      (node (ref "C241") (pin "2") (pinfunction "2_2") (pintype "passive"))
      (node (ref "C242") (pin "2") (pinfunction "2_2") (pintype "passive"))
      (node (ref "C243") (pin "2") (pinfunction "2_2") (pintype "passive"))
      (node (ref "C244") (pin "2") (pinfunction "2_2") (pintype "passive"))
      (node (ref "C245") (pin "2") (pinfunction "2_2") (pintype "passive"))
      (node (ref "C246") (pin "2") (pinfunction "2_2") (pintype "passive"))
      (node (ref "C247") (pin "2") (pinfunction "2_2") (pintype "passive"))
      (node (ref "C248") (pin "2") (pinfunction "2_2") (pintype "passive"))
      (node (ref "C249") (pin "2") (pinfunction "2_2") (pintype "passive"))
      (node (ref "C250") (pin "2") (pinfunction "2_2") (pintype "passive"))
      (node (ref "C251") (pin "2") (pinfunction "2_2") (pintype "passive"))
      (node (ref "R92") (pin "1") (pinfunction "1_1") (pintype "passive"))
      (node (ref "R95") (pin "1") (pinfunction "1_1") (pintype "passive"))
      (node (ref "R98") (pin "1") (pinfunction "1_1") (pintype "passive"))
      (node (ref "R99") (pin "1") (pinfunction "1_1") (pintype "passive"))
      (node (ref "U10") (pin "A4") (pinfunction "VDD2_A4_A4") (pintype "power_in"))
      (node (ref "U10") (pin "A9") (pinfunction "VDD2_A9_A9") (pintype "power_in"))
      (node (ref "U10") (pin "AA10") (pinfunction "VDDQ_AA10_AA10") (pintype "power_in"))
      (node (ref "U10") (pin "AA3") (pinfunction "VDDQ_AA3_AA3") (pintype "power_in"))
      (node (ref "U10") (pin "AA5") (pinfunction "VDDQ_AA5_AA5") (pintype "power_in"))
      (node (ref "U10") (pin "AA8") (pinfunction "VDDQ_AA8_AA8") (pintype "power_in"))
      (node (ref "U10") (pin "AB4") (pinfunction "VDD2_AB4_AB4") (pintype "power_in"))
      (node (ref "U10") (pin "AB9") (pinfunction "VDD2_AB9_AB9") (pintype "power_in"))
      (node (ref "U10") (pin "B10") (pinfunction "VDDQ_B10_B10") (pintype "power_in"))
      (node (ref "U10") (pin "B3") (pinfunction "VDDQ_B3_B3") (pintype "power_in"))
      (node (ref "U10") (pin "B5") (pinfunction "VDDQ_B5_B5") (pintype "power_in"))
      (node (ref "U10") (pin "B8") (pinfunction "VDDQ_B8_B8") (pintype "power_in"))
      (node (ref "U10") (pin "D1") (pinfunction "VDDQ_D1_D1") (pintype "power_in"))
      (node (ref "U10") (pin "D12") (pinfunction "VDDQ_D12_D12") (pintype "power_in"))
      (node (ref "U10") (pin "D5") (pinfunction "VDDQ_D5_D5") (pintype "power_in"))
      (node (ref "U10") (pin "D8") (pinfunction "VDDQ_D8_D8") (pintype "power_in"))
      (node (ref "U10") (pin "F10") (pinfunction "VDDQ_F10_F10") (pintype "power_in"))
      (node (ref "U10") (pin "F3") (pinfunction "VDDQ_F3_F3") (pintype "power_in"))
      (node (ref "U10") (pin "F5") (pinfunction "VDD2_F5_F5") (pintype "power_in"))
      (node (ref "U10") (pin "F8") (pinfunction "VDD2_F8_F8") (pintype "power_in"))
      (node (ref "U10") (pin "H1") (pinfunction "VDD2_H1_H1") (pintype "power_in"))
      (node (ref "U10") (pin "H12") (pinfunction "VDD2_H12_H12") (pintype "power_in"))
      (node (ref "U10") (pin "H5") (pinfunction "VDD2_H5_H5") (pintype "power_in"))
      (node (ref "U10") (pin "H8") (pinfunction "VDD2_H8_H8") (pintype "power_in"))
      (node (ref "U10") (pin "K1") (pinfunction "VDD2_K1_K1") (pintype "power_in"))
      (node (ref "U10") (pin "K10") (pinfunction "VDD2_K10_K10") (pintype "power_in"))
      (node (ref "U10") (pin "K12") (pinfunction "VDD2_K12_K12") (pintype "power_in"))
      (node (ref "U10") (pin "K3") (pinfunction "VDD2_K3_K3") (pintype "power_in"))
      (node (ref "U10") (pin "N1") (pinfunction "VDD2_N1_N1") (pintype "power_in"))
      (node (ref "U10") (pin "N10") (pinfunction "VDD2_N10_N10") (pintype "power_in"))
      (node (ref "U10") (pin "N12") (pinfunction "VDD2_N12_N12") (pintype "power_in"))
      (node (ref "U10") (pin "N3") (pinfunction "VDD2_N3_N3") (pintype "power_in"))
      (node (ref "U10") (pin "R1") (pinfunction "VDD2_R1_R1") (pintype "power_in"))
      (node (ref "U10") (pin "R12") (pinfunction "VDD2_R12_R12") (pintype "power_in"))
      (node (ref "U10") (pin "R5") (pinfunction "VDD2_R5_R5") (pintype "power_in"))
      (node (ref "U10") (pin "R8") (pinfunction "VDD2_R8_R8") (pintype "power_in"))
      (node (ref "U10") (pin "U10") (pinfunction "VDDQ_U10_U10") (pintype "power_in"))
      (node (ref "U10") (pin "U3") (pinfunction "VDDQ_U3_U3") (pintype "power_in"))
      (node (ref "U10") (pin "U5") (pinfunction "VDD2_U5_U5") (pintype "power_in"))
      (node (ref "U10") (pin "U8") (pinfunction "VDD2_U8_U8") (pintype "power_in"))
      (node (ref "U10") (pin "W1") (pinfunction "VDDQ_W1_W1") (pintype "power_in"))
      (node (ref "U10") (pin "W12") (pinfunction "VDDQ_W12_W12") (pintype "power_in"))
      (node (ref "U10") (pin "W5") (pinfunction "VDDQ_W5_W5") (pintype "power_in"))
      (node (ref "U10") (pin "W8") (pinfunction "VDDQ_W8_W8") (pintype "power_in"))
    )
    (net (code "84") (name "VDD_1V8") (class "Default")
      (node (ref "C230") (pin "2") (pinfunction "2_2") (pintype "passive"))
      (node (ref "C231") (pin "2") (pinfunction "2_2") (pintype "passive"))
      (node (ref "C232") (pin "2") (pinfunction "2_2") (pintype "passive"))
      (node (ref "C233") (pin "2") (pinfunction "2_2") (pintype "passive"))
      (node (ref "C234") (pin "2") (pinfunction "2_2") (pintype "passive"))
      (node (ref "C235") (pin "2") (pinfunction "2_2") (pintype "passive"))
      (node (ref "U10") (pin "F1") (pinfunction "VDD1_F1_F1") (pintype "power_in"))
      (node (ref "U10") (pin "F12") (pinfunction "VDD1_F12_F12") (pintype "power_in"))
      (node (ref "U10") (pin "G4") (pinfunction "VDD1_G4_G4") (pintype "power_in"))
      (node (ref "U10") (pin "G9") (pinfunction "VDD1_G9_G9") (pintype "power_in"))
      (node (ref "U10") (pin "T4") (pinfunction "VDD1_T4_T4") (pintype "power_in"))
      (node (ref "U10") (pin "T9") (pinfunction "VDD1_T9_T9") (pintype "power_in"))
      (node (ref "U10") (pin "U1") (pinfunction "VDD1_U1_U1") (pintype "power_in"))
      (node (ref "U10") (pin "U12") (pinfunction "VDD1_U12_U12") (pintype "power_in"))
    )
    (net (code "85") (name "unconnected-(U10A-DNU_A1-PadA1)") (class "Default")
      (node (ref "U10") (pin "A1") (pinfunction "DNU_A1_A1") (pintype "passive+no_connect"))
    )
    (net (code "86") (name "unconnected-(U10A-DNU_A2-PadA2)") (class "Default")
      (node (ref "U10") (pin "A2") (pinfunction "DNU_A2_A2") (pintype "passive+no_connect"))
    )
    (net (code "87") (name "unconnected-(U10A-DNU_A11-PadA11)") (class "Default")
      (node (ref "U10") (pin "A11") (pinfunction "DNU_A11_A11") (pintype "passive+no_connect"))
    )
    (net (code "88") (name "unconnected-(U10A-DNU_A12-PadA12)") (class "Default")
      (node (ref "U10") (pin "A12") (pinfunction "DNU_A12_A12") (pintype "passive+no_connect"))
    )
    (net (code "89") (name "unconnected-(U10A-DNU_AA1-PadAA1)") (class "Default")
      (node (ref "U10") (pin "AA1") (pinfunction "DNU_AA1_AA1") (pintype "passive+no_connect"))
    )
    (net (code "90") (name "unconnected-(U10A-DNU_AA12-PadAA12)") (class "Default")
      (node (ref "U10") (pin "AA12") (pinfunction "DNU_AA12_AA12") (pintype "passive+no_connect"))
    )
    (net (code "91") (name "unconnected-(U10A-DNU_AB1-PadAB1)") (class "Default")
      (node (ref "U10") (pin "AB1") (pinfunction "DNU_AB1_AB1") (pintype "passive+no_connect"))
    )
    (net (code "92") (name "unconnected-(U10A-DNU_AB2-PadAB2)") (class "Default")
      (node (ref "U10") (pin "AB2") (pinfunction "DNU_AB2_AB2") (pintype "passive+no_connect"))
    )
    (net (code "93") (name "unconnected-(U10A-DNU_AB11-PadAB11)") (class "Default")
      (node (ref "U10") (pin "AB11") (pinfunction "DNU_AB11_AB11") (pintype "passive+no_connect"))
    )
    (net (code "94") (name "unconnected-(U10A-DNU_AB12-PadAB12)") (class "Default")
      (node (ref "U10") (pin "AB12") (pinfunction "DNU_AB12_AB12") (pintype "passive+no_connect"))
    )
    (net (code "95") (name "unconnected-(U10A-DNU_B1-PadB1)") (class "Default")
      (node (ref "U10") (pin "B1") (pinfunction "DNU_B1_B1") (pintype "passive+no_connect"))
    )
    (net (code "96") (name "unconnected-(U10A-DNU_B12-PadB12)") (class "Default")
      (node (ref "U10") (pin "B12") (pinfunction "DNU_B12_B12") (pintype "passive+no_connect"))
    )
    (net (code "97") (name "unconnected-(U10A-NC_G11-PadG11)") (class "Default")
      (node (ref "U10") (pin "G11") (pinfunction "NC_G11_G11") (pintype "passive+no_connect"))
    )
    (net (code "98") (name "unconnected-(U10A-NC_K5-PadK5)") (class "Default")
      (node (ref "U10") (pin "K5") (pinfunction "NC_K5_K5") (pintype "passive+no_connect"))
    )
    (net (code "99") (name "unconnected-(U10A-NC_K8-PadK8)") (class "Default")
      (node (ref "U10") (pin "K8") (pinfunction "NC_K8_K8") (pintype "passive+no_connect"))
    )
    (net (code "100") (name "unconnected-(U10A-NC_N5-PadN5)") (class "Default")
      (node (ref "U10") (pin "N5") (pinfunction "NC_N5_N5") (pintype "passive+no_connect"))
    )
    (net (code "101") (name "unconnected-(U10A-NC_N8-PadN8)") (class "Default")
      (node (ref "U10") (pin "N8") (pinfunction "NC_N8_N8") (pintype "passive+no_connect"))
    )
  )
)
